# Buffer.net
KiCad netlist of a schematic drawn in Altium Designer
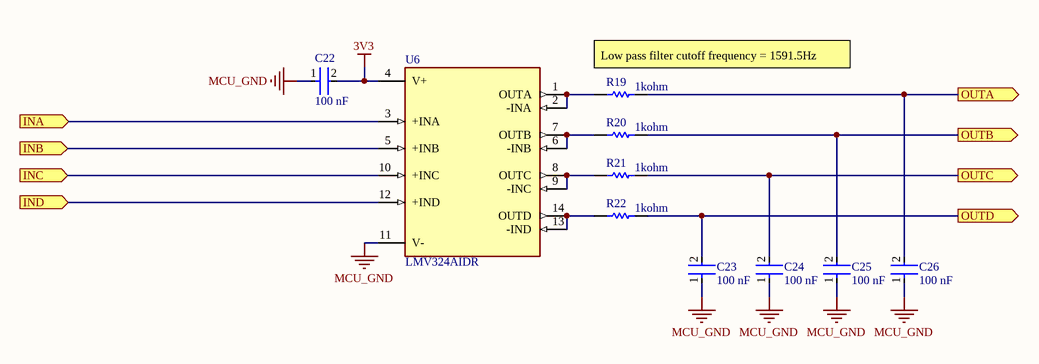
[diagram p0: Buffer.SchDoc]

(export (version "E")
  (design (tool "Eeschema 10.0.6"))
  (components
    (comp (ref "C22")
      (value "CC0603KRX7R7BB104")
      (footprint "FP-CC0603-DA-MFG")
      (description "CAP CER 0.1UF 16V X7R 0603")
      (fields
        (field (name "OCTOPART") "https://octopart.com/cc0603krx7r7bb104-yageo-192941")
        (field (name "TOLERANCE") "0.1")
        (field (name "CAPACITANCE") "100 nF")
      )
      (libsource (lib "Altium Content Vault") (part "11868f565c42a9108669ba33697ecf6"))
    )
    (comp (ref "C23")
      (value "CC0603KRX7R7BB104")
      (footprint "FP-CC0603-DA-MFG")
      (description "CAP CER 0.1UF 16V X7R 0603")
      (fields
        (field (name "OCTOPART") "https://octopart.com/cc0603krx7r7bb104-yageo-192941")
        (field (name "TOLERANCE") "0.1")
        (field (name "CAPACITANCE") "100 nF")
      )
      (libsource (lib "Altium Content Vault") (part "11868f565c42a9108669ba33697ecf6"))
    )
    (comp (ref "C24")
      (value "CC0603KRX7R7BB104")
      (footprint "FP-CC0603-DA-MFG")
      (description "CAP CER 0.1UF 16V X7R 0603")
      (fields
        (field (name "OCTOPART") "https://octopart.com/cc0603krx7r7bb104-yageo-192941")
        (field (name "TOLERANCE") "0.1")
        (field (name "CAPACITANCE") "100 nF")
      )
      (libsource (lib "Altium Content Vault") (part "11868f565c42a9108669ba33697ecf6"))
    )
    (comp (ref "C25")
      (value "CC0603KRX7R7BB104")
      (footprint "FP-CC0603-DA-MFG")
      (description "CAP CER 0.1UF 16V X7R 0603")
      (fields
        (field (name "OCTOPART") "https://octopart.com/cc0603krx7r7bb104-yageo-192941")
        (field (name "TOLERANCE") "0.1")
        (field (name "CAPACITANCE") "100 nF")
      )
      (libsource (lib "Altium Content Vault") (part "11868f565c42a9108669ba33697ecf6"))
    )
    (comp (ref "C26")
      (value "CC0603KRX7R7BB104")
      (footprint "FP-CC0603-DA-MFG")
      (description "CAP CER 0.1UF 16V X7R 0603")
      (fields
        (field (name "OCTOPART") "https://octopart.com/cc0603krx7r7bb104-yageo-192941")
        (field (name "TOLERANCE") "0.1")
        (field (name "CAPACITANCE") "100 nF")
      )
      (libsource (lib "Altium Content Vault") (part "11868f565c42a9108669ba33697ecf6"))
    )
    (comp (ref "R19")
      (value "RC0603JR-071KL")
      (footprint "RESC1608X55X25ML10T15")
      (description "Chip Resistor, 1 KOhm, +/- 5%, 0.063 W, -55 to 155 degC, 0603 (1608 Metric), RoHS, Tape and Reel")
      (fields (field (name "RESISTANCE") "1kohm") (field (name "MANUFACTURER") "Yageo"))
      (libsource (lib "Altium Content Vault") (part "RES-2"))
    )
    (comp (ref "R20")
      (value "RC0603JR-071KL")
      (footprint "RESC1608X55X25ML10T15")
      (description "Chip Resistor, 1 KOhm, +/- 5%, 0.063 W, -55 to 155 degC, 0603 (1608 Metric), RoHS, Tape and Reel")
      (fields (field (name "RESISTANCE") "1kohm") (field (name "MANUFACTURER") "Yageo"))
      (libsource (lib "Altium Content Vault") (part "RES-2"))
    )
    (comp (ref "R21")
      (value "RC0603JR-071KL")
      (footprint "RESC1608X55X25ML10T15")
      (description "Chip Resistor, 1 KOhm, +/- 5%, 0.063 W, -55 to 155 degC, 0603 (1608 Metric), RoHS, Tape and Reel")
      (fields (field (name "RESISTANCE") "1kohm") (field (name "MANUFACTURER") "Yageo"))
      (libsource (lib "Altium Content Vault") (part "RES-2"))
    )
    (comp (ref "R22")
      (value "RC0603JR-071KL")
      (footprint "RESC1608X55X25ML10T15")
      (description "Chip Resistor, 1 KOhm, +/- 5%, 0.063 W, -55 to 155 degC, 0603 (1608 Metric), RoHS, Tape and Reel")
      (fields (field (name "RESISTANCE") "1kohm") (field (name "MANUFACTURER") "Yageo"))
      (libsource (lib "Altium Content Vault") (part "RES-2"))
    )
    (comp (ref "U6")
      (value "LMV324AIDR")
      (footprint "PcbLib2:SOIC127P600X175-14N")
      (description "LMV324A, Quad Low-Voltage Rail-to-Rail Output Operational Amplifier 14-SOIC -40 to 125")
      (fields (field (name "MF") "Texas Instruments"))
      (libsource (lib "Schlib2") (part "LMV324AIDR"))
    )
  )
  (nets
    (net (code "1") (name "/INA") (class "Default")
      (node (ref "U6") (pin "3") (pinfunction "+INA_3") (pintype "input"))
    )
    (net (code "2") (name "/INB") (class "Default")
      (node (ref "U6") (pin "5") (pinfunction "+INB_5") (pintype "input"))
    )
    (net (code "3") (name "/INC") (class "Default")
      (node (ref "U6") (pin "10") (pinfunction "+INC_10") (pintype "input"))
    )
    (net (code "4") (name "/IND") (class "Default")
      (node (ref "U6") (pin "12") (pinfunction "+IND_12") (pintype "input"))
    )
    (net (code "5") (name "/OUTA") (class "Default")
      (node (ref "C26") (pin "2") (pinfunction "2_2") (pintype "passive"))
      (node (ref "R19") (pin "2") (pinfunction "2_2") (pintype "passive"))
    )
    (net (code "6") (name "/OUTB") (class "Default")
      (node (ref "C25") (pin "2") (pinfunction "2_2") (pintype "passive"))
      (node (ref "R20") (pin "2") (pinfunction "2_2") (pintype "passive"))
    )
    (net (code "7") (name "/OUTC") (class "Default")
      (node (ref "C24") (pin "2") (pinfunction "2_2") (pintype "passive"))
      (node (ref "R21") (pin "2") (pinfunction "2_2") (pintype "passive"))
    )
    (net (code "8") (name "/OUTD") (class "Default")
      (node (ref "C23") (pin "2") (pinfunction "2_2") (pintype "passive"))
      (node (ref "R22") (pin "2") (pinfunction "2_2") (pintype "passive"))
    )
    (net (code "9") (name "3V3") (class "Default")
      (node (ref "C22") (pin "2") (pinfunction "2_2") (pintype "passive"))
      (node (ref "U6") (pin "4") (pinfunction "V+_4") (pintype "power_in"))
    )
    (net (code "10") (name "MCU_GND") (class "Default")
      (node (ref "C22") (pin "1") (pinfunction "1_1") (pintype "passive"))
      (node (ref "C23") (pin "1") (pinfunction "1_1") (pintype "passive"))
      (node (ref "C24") (pin "1") (pinfunction "1_1") (pintype "passive"))
      (node (ref "C25") (pin "1") (pinfunction "1_1") (pintype "passive"))
      (node (ref "C26") (pin "1") (pinfunction "1_1") (pintype "passive"))
      (node (ref "U6") (pin "11") (pinfunction "V-_11") (pintype "power_in"))
    )
    (net (code "11") (name "Net-(U6--INA)") (class "Default")
      (node (ref "R19") (pin "1") (pinfunction "1_1") (pintype "passive"))
      (node (ref "U6") (pin "1") (pinfunction "OUTA_1") (pintype "output"))
      (node (ref "U6") (pin "2") (pinfunction "-INA_2") (pintype "input"))
    )
    (net (code "12") (name "Net-(U6--INB)") (class "Default")
      (node (ref "R20") (pin "1") (pinfunction "1_1") (pintype "passive"))
      (node (ref "U6") (pin "6") (pinfunction "-INB_6") (pintype "input"))
      (node (ref "U6") (pin "7") (pinfunction "OUTB_7") (pintype "output"))
    )
    (net (code "13") (name "Net-(U6--INC)") (class "Default")
      (node (ref "R21") (pin "1") (pinfunction "1_1") (pintype "passive"))
      (node (ref "U6") (pin "8") (pinfunction "OUTC_8") (pintype "output"))
      (node (ref "U6") (pin "9") (pinfunction "-INC_9") (pintype "input"))
    )
    (net (code "14") (name "Net-(U6--IND)") (class "Default")
      (node (ref "R22") (pin "1") (pinfunction "1_1") (pintype "passive"))
      (node (ref "U6") (pin "13") (pinfunction "-IND_13") (pintype "input"))
      (node (ref "U6") (pin "14") (pinfunction "OUTD_14") (pintype "output"))
    )
  )
)
